# ETH_CON.net
KiCad netlist of a schematic drawn in Altium Designer
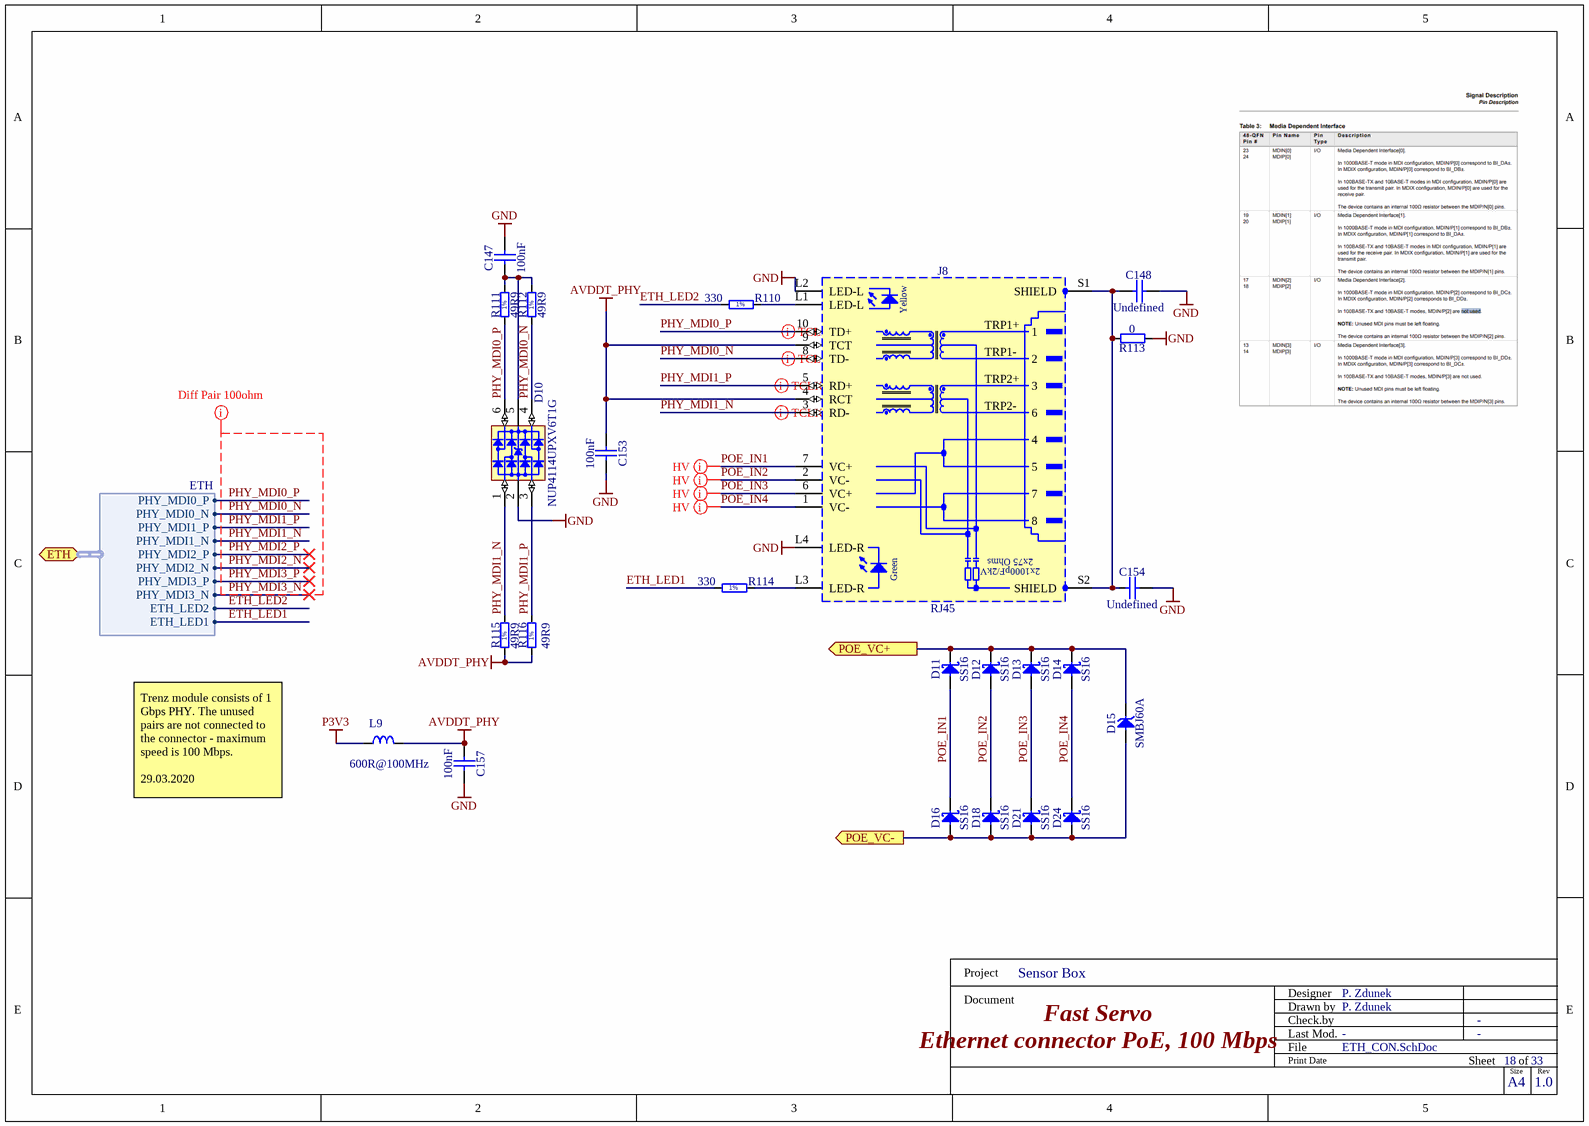
[diagram p0: ETH_CON.SchDoc]

(export (version "E")
  (design (tool "Eeschema 10.0.6"))
  (components
    (comp (ref "C147")
      (value "100nF")
      (footprint "CAPC1005X55N")
      (description "Non-polarised capacitor")
      (fields
        (field (name "PART NUMBER") "CC0402_100NF_16V_10%_X5R")
        (field (name "VOLTAGE") "16V")
        (field (name "AUTHOR") "CERN DEM JLC")
      )
      (libsource (lib "Capacitors") (part "Capacitor - non polarized"))
    )
    (comp (ref "C148")
      (value "Undefined")
      (footprint "CAPC2012X135N")
      (description "Non-polarised capacitor")
      (fields (field (name "PART NUMBER") "CC0805_NO-VALUE") (field (name "AUTHOR") "CERN DEM JLC"))
      (libsource (lib "Capacitors") (part "Capacitor - non polarized"))
    )
    (comp (ref "C153")
      (value "100nF")
      (footprint "CAPC1005X55N")
      (description "Non-polarised capacitor")
      (fields
        (field (name "PART NUMBER") "CC0402_100NF_16V_10%_X5R")
        (field (name "VOLTAGE") "16V")
        (field (name "AUTHOR") "CERN DEM JLC")
      )
      (libsource (lib "Capacitors") (part "Capacitor - non polarized"))
    )
    (comp (ref "C154")
      (value "Undefined")
      (footprint "CAPC2012X135N")
      (description "Non-polarised capacitor")
      (fields (field (name "PART NUMBER") "CC0805_NO-VALUE") (field (name "AUTHOR") "CERN DEM JLC"))
      (libsource (lib "Capacitors") (part "Capacitor - non polarized"))
    )
    (comp (ref "C157")
      (value "100nF")
      (footprint "CAPC1005X55N")
      (description "Non-polarised capacitor")
      (fields
        (field (name "PART NUMBER") "CC0402_100NF_16V_10%_X5R")
        (field (name "VOLTAGE") "16V")
        (field (name "AUTHOR") "CERN DEM JLC")
      )
      (libsource (lib "Capacitors") (part "Capacitor - non polarized"))
    )
    (comp (ref "D10")
      (value "NUP4114UPXV6T1G")
      (footprint "SOTFL50P160X60-6N")
      (fields
        (field (name "VOLTAGE") "5.5V")
        (field (name "MANUFACTURER") "ON SEMICONDUCTOR")
        (field (name "AUTHOR") "CERN DEM JLC")
      )
      (libsource (lib "ICs And Semiconductors") (part "NUP4114"))
    )
    (comp (ref "D11")
      (value "SS16")
      (footprint "DIOM5127X229N")
      (description "Schottky Diode")
      (fields
        (field (name "VOLTAGE") "60V")
        (field (name "POWER") "1A")
        (field (name "AUTHOR") "CERN DEM JLC")
      )
      (libsource (lib "ICs And Semiconductors") (part "Diode Schottky"))
    )
    (comp (ref "D12")
      (value "SS16")
      (footprint "DIOM5127X229N")
      (description "Schottky Diode")
      (fields
        (field (name "VOLTAGE") "60V")
        (field (name "POWER") "1A")
        (field (name "AUTHOR") "CERN DEM JLC")
      )
      (libsource (lib "ICs And Semiconductors") (part "Diode Schottky"))
    )
    (comp (ref "D13")
      (value "SS16")
      (footprint "DIOM5127X229N")
      (description "Schottky Diode")
      (fields
        (field (name "VOLTAGE") "60V")
        (field (name "POWER") "1A")
        (field (name "AUTHOR") "CERN DEM JLC")
      )
      (libsource (lib "ICs And Semiconductors") (part "Diode Schottky"))
    )
    (comp (ref "D14")
      (value "SS16")
      (footprint "DIOM5127X229N")
      (description "Schottky Diode")
      (fields
        (field (name "VOLTAGE") "60V")
        (field (name "POWER") "1A")
        (field (name "AUTHOR") "CERN DEM JLC")
      )
      (libsource (lib "ICs And Semiconductors") (part "Diode Schottky"))
    )
    (comp (ref "D15")
      (value "SMBJ60A")
      (footprint "DIOM5336X265N")
      (description "Zener Diode")
      (fields
        (field (name "VOLTAGE") "60V")
        (field (name "POWER") "600W")
        (field (name "AUTHOR") "CERN DEM JLC")
      )
      (libsource (lib "ICs And Semiconductors") (part "Diode Zener"))
    )
    (comp (ref "D16")
      (value "SS16")
      (footprint "DIOM5127X229N")
      (description "Schottky Diode")
      (fields
        (field (name "VOLTAGE") "60V")
        (field (name "POWER") "1A")
        (field (name "AUTHOR") "CERN DEM JLC")
      )
      (libsource (lib "ICs And Semiconductors") (part "Diode Schottky"))
    )
    (comp (ref "D18")
      (value "SS16")
      (footprint "DIOM5127X229N")
      (description "Schottky Diode")
      (fields
        (field (name "VOLTAGE") "60V")
        (field (name "POWER") "1A")
        (field (name "AUTHOR") "CERN DEM JLC")
      )
      (libsource (lib "ICs And Semiconductors") (part "Diode Schottky"))
    )
    (comp (ref "D21")
      (value "SS16")
      (footprint "DIOM5127X229N")
      (description "Schottky Diode")
      (fields
        (field (name "VOLTAGE") "60V")
        (field (name "POWER") "1A")
        (field (name "AUTHOR") "CERN DEM JLC")
      )
      (libsource (lib "ICs And Semiconductors") (part "Diode Schottky"))
    )
    (comp (ref "D24")
      (value "SS16")
      (footprint "DIOM5127X229N")
      (description "Schottky Diode")
      (fields
        (field (name "VOLTAGE") "60V")
        (field (name "POWER") "1A")
        (field (name "AUTHOR") "CERN DEM JLC")
      )
      (libsource (lib "ICs And Semiconductors") (part "Diode Schottky"))
    )
    (comp (ref "J8")
      (value "RJ45")
      (footprint "ABRACON_ARJM11C7-114-BA-EW2")
      (description "MagJack 10/100BaseT, PoE+, 1X1, OG/Y, -40 to 85*C, Tab Up, RoHS")
      (fields
        (field (name "PART NUMBER") "ARJM11C7-114-BA-EW2")
        (field (name "MANUFACTURER") "Abracon")
        (field (name "AUTHOR") "GK")
      )
      (libsource (lib "Stabilizer") (part "CON_ETH_POE_ARJM11C7"))
    )
    (comp (ref "L9")
      (value "600R@100MHz")
      (footprint "INDC1005X55N")
      (description "Inductor")
      (fields
        (field (name "PART NUMBER") "IND0402_MURATA_BLM15HD601SN1")
        (field (name "POWER") "300mA")
        (field (name "AUTHOR") "CERN DEM JLC")
      )
      (libsource (lib "Inductors & Transformers") (part "Inductor"))
    )
    (comp (ref "R110")
      (value "330")
      (footprint "RESC1005X40N")
      (description "Resistor - 1%")
      (fields
        (field (name "PART NUMBER") "R0402_330R_1%_0.0625W_100PPM")
        (field (name "POWER") "0.0625W")
        (field (name "AUTHOR") "CERN DEM JLC")
      )
      (libsource (lib "Resistors") (part "Resistor - 1%"))
    )
    (comp (ref "R111")
      (value "49R9")
      (footprint "RESC1005X40N")
      (description "Resistor - 1%")
      (fields
        (field (name "PART NUMBER") "R0402_49R9_1%_0.0625W_100PPM")
        (field (name "POWER") "0.0625W")
        (field (name "AUTHOR") "CERN DEM JLC")
      )
      (libsource (lib "Resistors") (part "Resistor - 1%"))
    )
    (comp (ref "R112")
      (value "49R9")
      (footprint "RESC1005X40N")
      (description "Resistor - 1%")
      (fields
        (field (name "PART NUMBER") "R0402_49R9_1%_0.0625W_100PPM")
        (field (name "POWER") "0.0625W")
        (field (name "AUTHOR") "CERN DEM JLC")
      )
      (libsource (lib "Resistors") (part "Resistor - 1%"))
    )
    (comp (ref "R113")
      (value "0")
      (footprint "RESC1608X55N")
      (description "Resistor")
      (fields
        (field (name "PART NUMBER") "R0603_0R_JUMPER")
        (field (name "MANUFACTURER") "GENERIC")
        (field (name "AUTHOR") "CERN DEM JLC")
      )
      (libsource (lib "Resistors") (part "Resistor"))
    )
    (comp (ref "R114")
      (value "330")
      (footprint "RESC1005X40N")
      (description "Resistor - 1%")
      (fields
        (field (name "PART NUMBER") "R0402_330R_1%_0.0625W_100PPM")
        (field (name "POWER") "0.0625W")
        (field (name "AUTHOR") "CERN DEM JLC")
      )
      (libsource (lib "Resistors") (part "Resistor - 1%"))
    )
    (comp (ref "R115")
      (value "49R9")
      (footprint "RESC1005X40N")
      (description "Resistor - 1%")
      (fields
        (field (name "PART NUMBER") "R0402_49R9_1%_0.0625W_100PPM")
        (field (name "POWER") "0.0625W")
        (field (name "AUTHOR") "CERN DEM JLC")
      )
      (libsource (lib "Resistors") (part "Resistor - 1%"))
    )
    (comp (ref "R116")
      (value "49R9")
      (footprint "RESC1005X40N")
      (description "Resistor - 1%")
      (fields
        (field (name "PART NUMBER") "R0402_49R9_1%_0.0625W_100PPM")
        (field (name "POWER") "0.0625W")
        (field (name "AUTHOR") "CERN DEM JLC")
      )
      (libsource (lib "Resistors") (part "Resistor - 1%"))
    )
  )
  (nets
    (net (code "2") (name "/ETH_LED1") (class "Default")
      (node (ref "R114") (pin "1") (pinfunction "1_1") (pintype "passive"))
    )
    (net (code "3") (name "/ETH_LED2") (class "Default")
      (node (ref "R110") (pin "1") (pinfunction "1_1") (pintype "passive"))
    )
    (net (code "4") (name "/PHY_MDI0_N") (class "Default")
      (node (ref "D10") (pin "4") (pinfunction "I/O3_4") (pintype "bidirectional"))
      (node (ref "J8") (pin "8") (pinfunction "TD-_8") (pintype "bidirectional"))
      (node (ref "R112") (pin "1") (pinfunction "1_1") (pintype "passive"))
    )
    (net (code "5") (name "/PHY_MDI0_P") (class "Default")
      (node (ref "D10") (pin "6") (pinfunction "I/O4_6") (pintype "bidirectional"))
      (node (ref "J8") (pin "10") (pinfunction "TD+_10") (pintype "bidirectional"))
      (node (ref "R111") (pin "1") (pinfunction "1_1") (pintype "passive"))
    )
    (net (code "6") (name "/PHY_MDI1_N") (class "Default")
      (node (ref "D10") (pin "1") (pinfunction "I/O1_1") (pintype "bidirectional"))
      (node (ref "J8") (pin "3") (pinfunction "RD-_3") (pintype "bidirectional"))
      (node (ref "R115") (pin "2") (pinfunction "2_2") (pintype "passive"))
    )
    (net (code "7") (name "/PHY_MDI1_P") (class "Default")
      (node (ref "D10") (pin "3") (pinfunction "I/O2_3") (pintype "bidirectional"))
      (node (ref "J8") (pin "5") (pinfunction "RD+_5") (pintype "bidirectional"))
      (node (ref "R116") (pin "2") (pinfunction "2_2") (pintype "passive"))
    )
    (net (code "12") (name "/POE_IN1") (class "Default")
      (node (ref "D11") (pin "2") (pinfunction "A_2") (pintype "passive"))
      (node (ref "D16") (pin "1") (pinfunction "C_1") (pintype "passive"))
      (node (ref "J8") (pin "7") (pinfunction "VC+_7") (pintype "passive"))
    )
    (net (code "13") (name "/POE_IN2") (class "Default")
      (node (ref "D12") (pin "2") (pinfunction "A_2") (pintype "passive"))
      (node (ref "D18") (pin "1") (pinfunction "C_1") (pintype "passive"))
      (node (ref "J8") (pin "2") (pinfunction "VC-_2") (pintype "passive"))
    )
    (net (code "14") (name "/POE_IN3") (class "Default")
      (node (ref "D13") (pin "2") (pinfunction "A_2") (pintype "passive"))
      (node (ref "D21") (pin "1") (pinfunction "C_1") (pintype "passive"))
      (node (ref "J8") (pin "6") (pinfunction "VC+_6") (pintype "passive"))
    )
    (net (code "15") (name "/POE_IN4") (class "Default")
      (node (ref "D14") (pin "2") (pinfunction "A_2") (pintype "passive"))
      (node (ref "D24") (pin "1") (pinfunction "C_1") (pintype "passive"))
      (node (ref "J8") (pin "1") (pinfunction "VC-_1") (pintype "passive"))
    )
    (net (code "16") (name "/POE_VC+") (class "Default")
      (node (ref "D11") (pin "1") (pinfunction "C_1") (pintype "passive"))
      (node (ref "D12") (pin "1") (pinfunction "C_1") (pintype "passive"))
      (node (ref "D13") (pin "1") (pinfunction "C_1") (pintype "passive"))
      (node (ref "D14") (pin "1") (pinfunction "C_1") (pintype "passive"))
      (node (ref "D15") (pin "1") (pinfunction "C_1") (pintype "passive"))
    )
    (net (code "17") (name "/POE_VC-") (class "Default")
      (node (ref "D15") (pin "2") (pinfunction "A_2") (pintype "passive"))
      (node (ref "D16") (pin "2") (pinfunction "A_2") (pintype "passive"))
      (node (ref "D18") (pin "2") (pinfunction "A_2") (pintype "passive"))
      (node (ref "D21") (pin "2") (pinfunction "A_2") (pintype "passive"))
      (node (ref "D24") (pin "2") (pinfunction "A_2") (pintype "passive"))
    )
    (net (code "19") (name "AVDDT_PHY") (class "Default")
      (node (ref "C153") (pin "2") (pinfunction "2_2") (pintype "passive"))
      (node (ref "C157") (pin "1") (pinfunction "1_1") (pintype "passive"))
      (node (ref "J8") (pin "4") (pinfunction "RCT_4") (pintype "bidirectional"))
      (node (ref "J8") (pin "9") (pinfunction "TCT_9") (pintype "bidirectional"))
      (node (ref "L9") (pin "2") (pinfunction "2_2") (pintype "passive"))
      (node (ref "R115") (pin "1") (pinfunction "1_1") (pintype "passive"))
      (node (ref "R116") (pin "1") (pinfunction "1_1") (pintype "passive"))
    )
    (net (code "20") (name "GND") (class "Default")
      (node (ref "C147") (pin "2") (pinfunction "2_2") (pintype "passive"))
      (node (ref "C148") (pin "2") (pinfunction "2_2") (pintype "passive"))
      (node (ref "C153") (pin "1") (pinfunction "1_1") (pintype "passive"))
      (node (ref "C154") (pin "2") (pinfunction "2_2") (pintype "passive"))
      (node (ref "C157") (pin "2") (pinfunction "2_2") (pintype "passive"))
      (node (ref "D10") (pin "2") (pinfunction "GND_2") (pintype "power_in"))
      (node (ref "J8") (pin "L2") (pinfunction "LED-L_L2") (pintype "passive"))
      (node (ref "J8") (pin "L4") (pinfunction "LED-R_L4") (pintype "passive"))
      (node (ref "R113") (pin "1") (pinfunction "1_1") (pintype "passive"))
    )
    (net (code "21") (name "Net-(C148-Pad1)") (class "Default")
      (node (ref "C148") (pin "1") (pinfunction "1_1") (pintype "passive"))
      (node (ref "C154") (pin "1") (pinfunction "1_1") (pintype "passive"))
      (node (ref "J8") (pin "S1") (pinfunction "SHIELD_S1") (pintype "power_in"))
      (node (ref "J8") (pin "S2") (pinfunction "SHIELD_S2") (pintype "power_in"))
      (node (ref "R113") (pin "2") (pinfunction "2_2") (pintype "passive"))
    )
    (net (code "22") (name "Net-(D10-VBUS)") (class "Default")
      (node (ref "C147") (pin "1") (pinfunction "1_1") (pintype "passive"))
      (node (ref "D10") (pin "5") (pinfunction "VBUS_5") (pintype "power_in"))
      (node (ref "R111") (pin "2") (pinfunction "2_2") (pintype "passive"))
      (node (ref "R112") (pin "2") (pinfunction "2_2") (pintype "passive"))
    )
    (net (code "23") (name "Net-(J8-LED-L-PadL1)") (class "Default")
      (node (ref "J8") (pin "L1") (pinfunction "LED-L_L1") (pintype "passive"))
      (node (ref "R110") (pin "2") (pinfunction "2_2") (pintype "passive"))
    )
    (net (code "24") (name "Net-(J8-LED-R-PadL3)") (class "Default")
      (node (ref "J8") (pin "L3") (pinfunction "LED-R_L3") (pintype "passive"))
      (node (ref "R114") (pin "2") (pinfunction "2_2") (pintype "passive"))
    )
    (net (code "25") (name "P3V3") (class "Default")
      (node (ref "L9") (pin "1") (pinfunction "1_1") (pintype "passive"))
    )
  )
)
